# MCISO-S03-V00-PSU5VB.net
KiCad netlist of a schematic drawn in Altium Designer
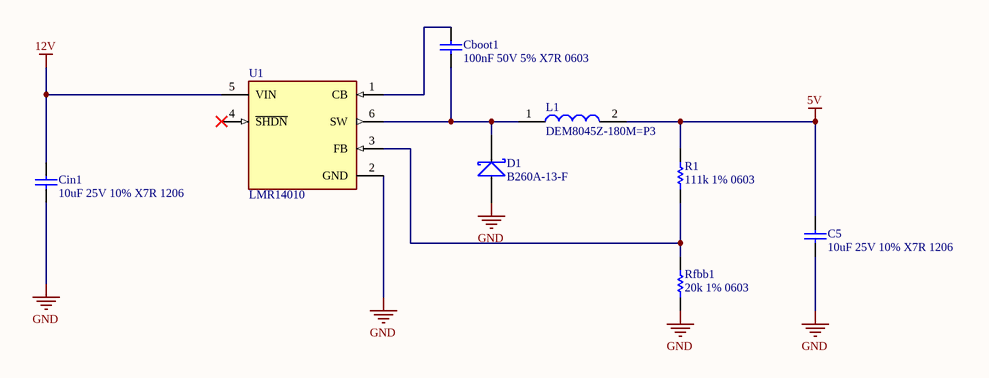
[diagram p0: MCISO-S03-V00-PSU5VB.SchDoc]

(export (version "E")
  (design (tool "Eeschema 10.0.6"))
  (components
    (comp (ref "C5")
      (value "10uF 25V 10% X7R 1206")
      (footprint "Cap_Ceramic_1206")
      (description "Capacitor, Ceramic, SMD, 10uF, 25V, 10%, X7R, 1206")
      (libsource (lib "QUTMS-MCISOLibrary") (part "10uF 25V 10% X7R 1206"))
    )
    (comp (ref "Cboot1")
      (value "100nF 50V 5% X7R 0603")
      (footprint "Cap_Ceramic_0603")
      (description "Capacitor, Ceramic, SMD, 100nF, 50V, 5%, X7R, 0603")
      (libsource (lib "StandardCapacitors") (part "100nF 50V 5% X7R 0603"))
    )
    (comp (ref "Cin1")
      (value "10uF 25V 10% X7R 1206")
      (footprint "Cap_Ceramic_1206")
      (description "Capacitor, Ceramic, SMD, 10uF, 25V, 10%, X7R, 1206")
      (libsource (lib "StandardCapacitors") (part "10uF 25V 10% X7R 1206"))
    )
    (comp (ref "D1")
      (value "B260A-13-F")
      (footprint "SMA")
      (description "Diode, Schottky Barrier Rectifier, 60 V, 2 A, B260A-13-F")
      (libsource (lib "QUTMS-MCISOLibrary") (part "B260A-13-F"))
    )
    (comp (ref "L1")
      (value "DEM8045Z-180M=P3")
      (footprint "SamacSys:1217ASH100MP3")
      (description "Inductor")
      (fields (field (name "MOUSER PART NUMBER") "81-DEM8045Z-180M=P3"))
      (libsource (lib "QUTMS-MCISOLibrary") (part "DEM8045Z-180M=P3"))
    )
    (comp (ref "R1")
      (value "111k 1% 0603")
      (footprint "Res_ThinFilm_0603")
      (description "Resistor, SMD, 111k, 0.1W, 1%, 0603")
      (libsource (lib "QUTMS-MCISOLibrary") (part "111k 1% 0603"))
    )
    (comp (ref "Rfbb1")
      (value "20k 1% 0603")
      (footprint "Res_ThinFilm_0603")
      (description "Resistor, SMD, 19k6, 0.1W, 5%, 0603")
      (libsource (lib "StandardResistors") (part "19k6 1% 0603"))
    )
    (comp (ref "U1")
      (value "LMR14010")
      (footprint "LMR14010")
      (libsource (lib "QUTMS-MCISOLibrary") (part "LMR14010"))
    )
  )
  (nets
    (net (code "1") (name "5V") (class "Default")
      (node (ref "C5") (pin "2") (pinfunction "2_2") (pintype "passive"))
      (node (ref "L1") (pin "2") (pinfunction "2_2") (pintype "passive"))
      (node (ref "R1") (pin "2") (pinfunction "2_2") (pintype "passive"))
    )
    (net (code "2") (name "12V") (class "Default")
      (node (ref "Cin1") (pin "2") (pinfunction "2_2") (pintype "passive"))
      (node (ref "U1") (pin "5") (pinfunction "VIN_5") (pintype "power_in"))
    )
    (net (code "3") (name "GND") (class "Default")
      (node (ref "C5") (pin "1") (pinfunction "1_1") (pintype "passive"))
      (node (ref "Cin1") (pin "1") (pinfunction "1_1") (pintype "passive"))
      (node (ref "D1") (pin "A") (pinfunction "A_A") (pintype "passive"))
      (node (ref "Rfbb1") (pin "1") (pinfunction "1_1") (pintype "passive"))
      (node (ref "U1") (pin "2") (pinfunction "GND_2") (pintype "power_in"))
    )
    (net (code "4") (name "Net-(U1-CB)") (class "Default")
      (node (ref "Cboot1") (pin "2") (pinfunction "2_2") (pintype "passive"))
      (node (ref "U1") (pin "1") (pinfunction "CB_1") (pintype "input"))
    )
    (net (code "5") (name "Net-(U1-FB)") (class "Default")
      (node (ref "R1") (pin "1") (pinfunction "1_1") (pintype "passive"))
      (node (ref "Rfbb1") (pin "2") (pinfunction "2_2") (pintype "passive"))
      (node (ref "U1") (pin "3") (pinfunction "FB_3") (pintype "input"))
    )
    (net (code "6") (name "Net-(U1-SW)") (class "Default")
      (node (ref "Cboot1") (pin "1") (pinfunction "1_1") (pintype "passive"))
      (node (ref "D1") (pin "K") (pinfunction "K_K") (pintype "passive"))
      (node (ref "L1") (pin "1") (pinfunction "1_1") (pintype "passive"))
      (node (ref "U1") (pin "6") (pinfunction "SW_6") (pintype "output"))
    )
    (net (code "7") (name "unconnected-(U1-~{SHDN}-Pad4)") (class "Default")
      (node (ref "U1") (pin "4") (pinfunction "~{SHDN}_4") (pintype "input+no_connect"))
    )
  )
)
